# newDCDC.net
KiCad netlist of a schematic drawn in EAGLE
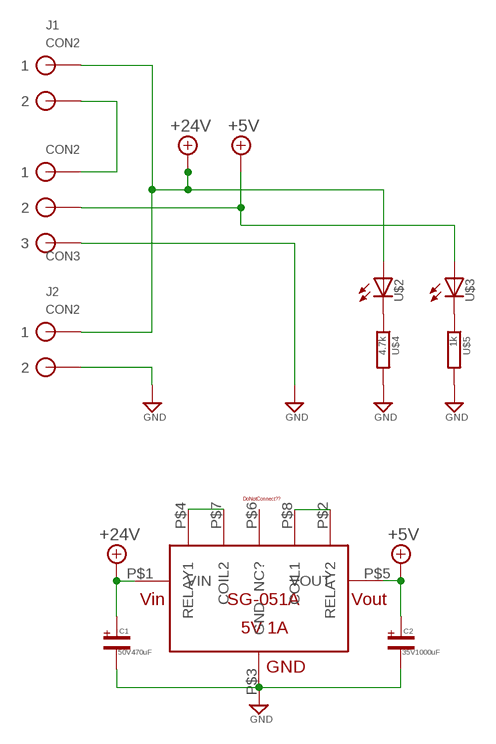
[diagram p0: schematic, sheet 1]

(export (version "E")
  (design (tool "Eeschema 10.0.6"))
  (components
    (comp (ref "C1")
      (value "50V470uF")
      (footprint "eagle-import:D=2,φ=10,5")
      (libsource (lib "eagle-import") (part "コンデンサ(電解)E5-10.5"))
    )
    (comp (ref "C2")
      (value "35V1000uF")
      (footprint "eagle-import:D=2,φ=13")
      (libsource (lib "eagle-import") (part "コンデンサ(電解)E5-13"))
    )
    (comp (ref "CON2")
      (value "CON3")
      (footprint "eagle-import:CON3")
      (libsource (lib "eagle-import") (part "CON3"))
    )
    (comp (ref "J1")
      (value "CON2")
      (footprint "eagle-import:CON2")
      (libsource (lib "eagle-import") (part "CON2"))
    )
    (comp (ref "J2")
      (value "CON2")
      (footprint "eagle-import:CON2")
      (libsource (lib "eagle-import") (part "CON2"))
    )
    (comp (ref "U$1")
      (value "SG-051A")
      (footprint "eagle-import:SG-051A")
      (libsource (lib "eagle-import") (part "SG-051A"))
    )
    (comp (ref "U$2")
      (value "LED(砲弾型)3")
      (footprint "eagle-import:LED3MM")
      (libsource (lib "eagle-import") (part "LED(砲弾型)3"))
    )
    (comp (ref "U$3")
      (value "LED(砲弾型)3")
      (footprint "eagle-import:LED3MM")
      (libsource (lib "eagle-import") (part "LED(砲弾型)3"))
    )
    (comp (ref "U$4")
      (value "4.7k")
      (footprint "eagle-import:0805(JIS2012)HAND")
      (libsource (lib "eagle-import") (part "抵抗0805"))
    )
    (comp (ref "U$5")
      (value "1k")
      (footprint "eagle-import:0805(JIS2012)HAND")
      (libsource (lib "eagle-import") (part "抵抗0805"))
    )
  )
  (nets
    (net (code "1") (name "+5V") (class "Default")
      (node (ref "C2") (pin "+") (pinfunction "+_+") (pintype "passive"))
      (node (ref "CON2") (pin "P$2") (pinfunction "2_P$2") (pintype "bidirectional"))
      (node (ref "U$1") (pin "P$5") (pinfunction "VOUT_P$5") (pintype "bidirectional"))
      (node (ref "U$3") (pin "A") (pinfunction "A_A") (pintype "passive"))
    )
    (net (code "2") (name "+24V") (class "Default")
      (node (ref "C1") (pin "+") (pinfunction "+_+") (pintype "passive"))
      (node (ref "J1") (pin "P$1") (pinfunction "1_P$1") (pintype "bidirectional"))
      (node (ref "J2") (pin "P$1") (pinfunction "1_P$1") (pintype "bidirectional"))
      (node (ref "U$1") (pin "P$1") (pinfunction "VIN_P$1") (pintype "bidirectional"))
      (node (ref "U$2") (pin "A") (pinfunction "A_A") (pintype "passive"))
    )
    (net (code "3") (name "GND") (class "Default")
      (node (ref "C1") (pin "-") (pinfunction "-_-") (pintype "passive"))
      (node (ref "C2") (pin "-") (pinfunction "-_-") (pintype "passive"))
      (node (ref "CON2") (pin "P$3") (pinfunction "3_P$3") (pintype "bidirectional"))
      (node (ref "J2") (pin "P$2") (pinfunction "2_P$2") (pintype "bidirectional"))
      (node (ref "U$1") (pin "P$3") (pinfunction "GND_P$3") (pintype "bidirectional"))
      (node (ref "U$4") (pin "2") (pinfunction "2_2") (pintype "passive"))
      (node (ref "U$5") (pin "2") (pinfunction "2_2") (pintype "passive"))
    )
    (net (code "4") (name "Net-(CON2-1)") (class "Default")
      (node (ref "CON2") (pin "P$1") (pinfunction "1_P$1") (pintype "bidirectional"))
      (node (ref "J1") (pin "P$2") (pinfunction "2_P$2") (pintype "bidirectional"))
    )
    (net (code "5") (name "Net-(U$1-COIL1)") (class "Default")
      (node (ref "U$1") (pin "P$2") (pinfunction "RELAY2_P$2") (pintype "bidirectional"))
      (node (ref "U$1") (pin "P$8") (pinfunction "COIL1_P$8") (pintype "bidirectional"))
    )
    (net (code "6") (name "Net-(U$1-COIL2)") (class "Default")
      (node (ref "U$1") (pin "P$4") (pinfunction "RELAY1_P$4") (pintype "bidirectional"))
      (node (ref "U$1") (pin "P$7") (pinfunction "COIL2_P$7") (pintype "bidirectional"))
    )
    (net (code "7") (name "Net-(U$2-PadK)") (class "Default")
      (node (ref "U$2") (pin "K") (pinfunction "K_K") (pintype "passive"))
      (node (ref "U$4") (pin "1") (pinfunction "1_1") (pintype "passive"))
    )
    (net (code "8") (name "Net-(U$3-PadK)") (class "Default")
      (node (ref "U$3") (pin "K") (pinfunction "K_K") (pintype "passive"))
      (node (ref "U$5") (pin "1") (pinfunction "1_1") (pintype "passive"))
    )
    (net (code "9") (name "unconnected-(U$1-NC?-PadP$6)") (class "Default")
      (node (ref "U$1") (pin "P$6") (pinfunction "NC?_P$6") (pintype "bidirectional"))
    )
  )
)
